# PCB_Slave_Traffic_Light.net
KiCad netlist of a schematic drawn in Altium Designer
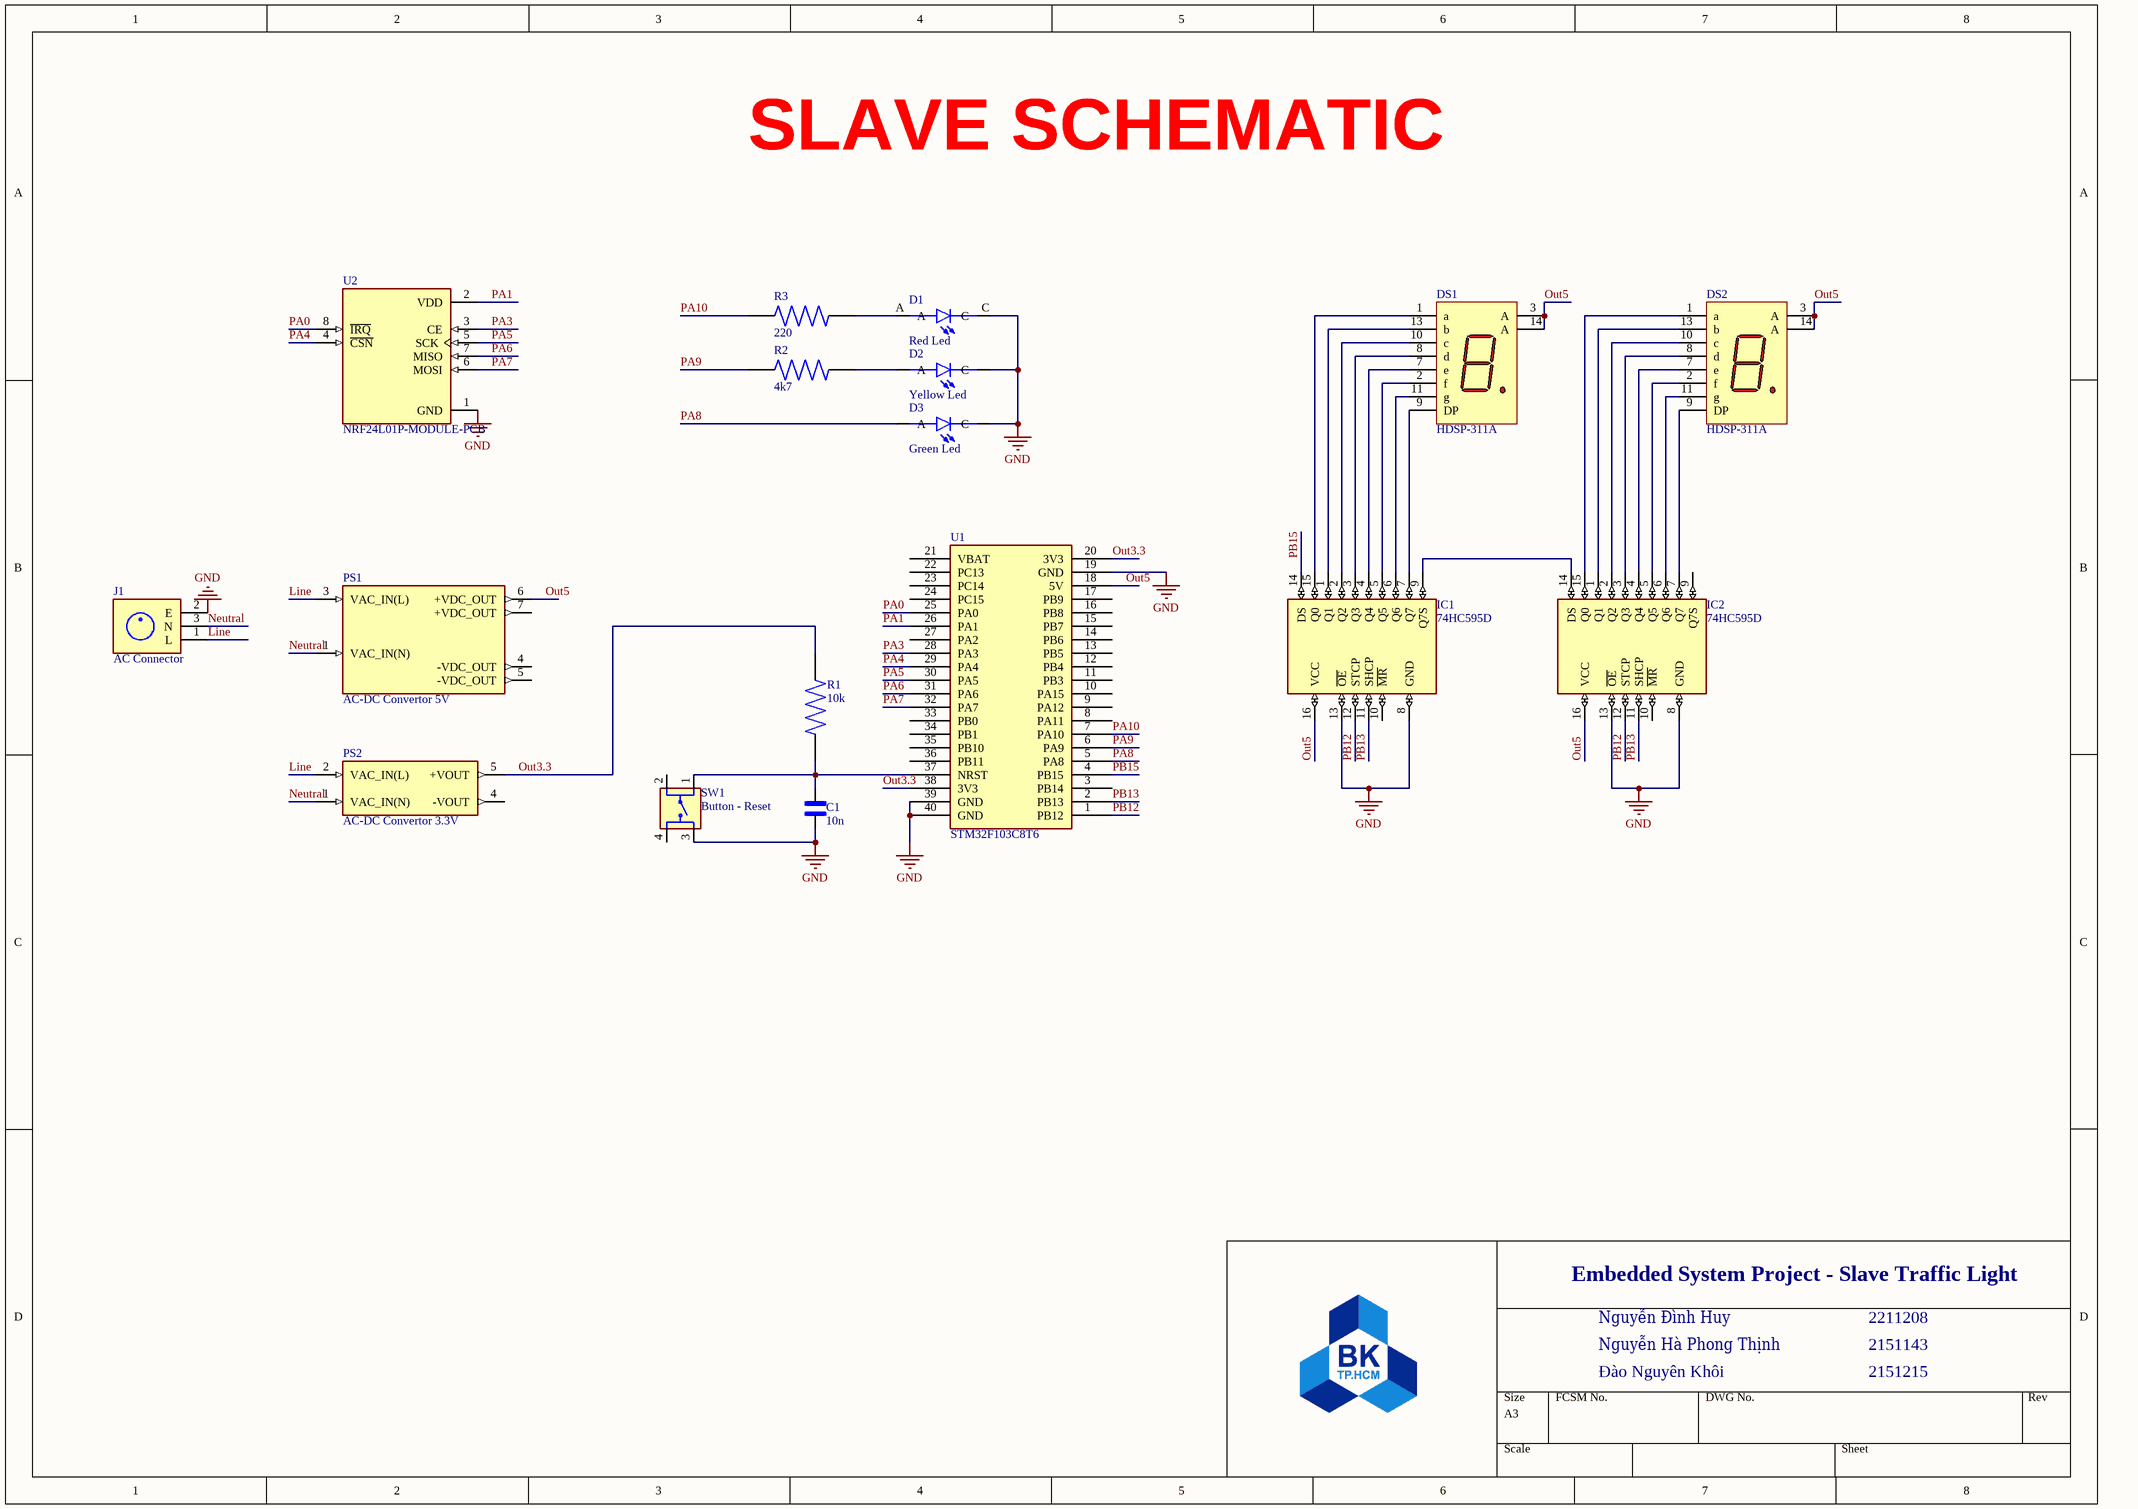
[diagram p0: PCB_Slave_Traffic_Light.SchDoc]

(export (version "E")
  (design (tool "Eeschema 10.0.6"))
  (components
    (comp (ref "C1")
      (value "10n")
      (footprint "CAPC1005X55N")
      (description "Multilayer Ceramic Capacitors MLCC - SMD/SMT")
      (fields (field (name "MF") "Murata") (field (name "MP") "GCM155R11H103KA40D"))
      (libsource (lib "Capacitor 10n") (part "GCM155R11H103KA40D"))
    )
    (comp (ref "D1")
      (value "Red Led")
      (footprint "LED_WP7113ID")
      (description "Red 617nm LED Indication - Discrete 2V Radial")
      (fields (field (name "MP") "WP7113ID") (field (name "MF") "Kingbright"))
      (libsource (lib "Red Led") (part "WP7113ID"))
    )
    (comp (ref "D2")
      (value "Yellow Led")
      (footprint "LED_WP7113SYD")
      (description "Yellow 590nm LED Indication - Discrete 2V Radial")
      (fields (field (name "MF") "Kingbright") (field (name "MP") "WP7113SYD"))
      (libsource (lib "Yellow Led") (part "WP7113SYD"))
    )
    (comp (ref "D3")
      (value "Green Led")
      (footprint "LED_WP7113GD")
      (description "Green 568nm LED Indication - Discrete 2.2V Radial")
      (fields (field (name "MF") "Kingbright") (field (name "MP") "WP7113GD"))
      (libsource (lib "Green Led") (part "WP7113GD"))
    )
    (comp (ref "DS1")
      (value "HDSP-311A")
      (footprint "F-10(14)")
      (description "10.16 mm Single Digit General Purpose AlGaAs Red 7-Segment Display: CA, RH DP")
      (fields (field (name "PUBLISHER") "Altium Limited"))
      (libsource (lib "Agilent LED Display 7-Segment, 1-Digit") (part "HDSP-311A"))
    )
    (comp (ref "DS2")
      (value "HDSP-311A")
      (footprint "F-10(14)")
      (description "10.16 mm Single Digit General Purpose AlGaAs Red 7-Segment Display: CA, RH DP")
      (fields (field (name "PUBLISHER") "Altium Limited"))
      (libsource (lib "Agilent LED Display 7-Segment, 1-Digit") (part "HDSP-311A"))
    )
    (comp (ref "IC1")
      (value "74HC595D")
      (footprint "SOIC127P600X175-16N")
      (description "Shift Register Single 8-Bit Serial to Serial/Parallel 16-Pin SOIC T/R")
      (fields (field (name "MF") "NXP Semiconductors"))
      (libsource (lib "74HC595D") (part "74HC595D"))
    )
    (comp (ref "IC2")
      (value "74HC595D")
      (footprint "SOIC127P600X175-16N")
      (description "Shift Register Single 8-Bit Serial to Serial/Parallel 16-Pin SOIC T/R")
      (fields (field (name "MF") "NXP Semiconductors"))
      (libsource (lib "74HC595D") (part "74HC595D"))
    )
    (comp (ref "J1")
      (value "AC Connector")
      (footprint "QUALTEK_703W-00/52")
      (fields (field (name "MP") "703W-00/52") (field (name "MF") "Qualtek"))
      (libsource (lib "AC Connector") (part "703W-00/52"))
    )
    (comp (ref "PS1")
      (value "AC-DC Convertor 5V")
      (footprint "CONV_RACM40-05SK/OF/PCB-T")
      (description "Open Frame AC DC Converters 1 Uitgang 5V - - - 6A 80 ~ 264 VAC, 120 ~ 370 VDC Input")
      (fields (field (name "MF") "Recom Power") (field (name "MP") "RACM40-05SK/OF/PCB-T"))
      (libsource (lib "AC-DC Converter") (part "RACM40-05SK/OF/PCB-T"))
    )
    (comp (ref "PS2")
      (value "AC-DC Convertor 3.3V")
      (footprint "CONV_RAC10-3.3SK/277")
      (description "10W AC/DC-Converter 'POWERLINE' 2x1 4kV reg")
      (fields (field (name "MF") "Recom Power") (field (name "MP") "RAC10-3.3SK/277"))
      (libsource (lib "AC-DC Converter 3.3V") (part "RAC10-3.3SK/277"))
    )
    (comp (ref "R1")
      (value "10k")
      (footprint "RESC2012X60N")
      (description "10 kOhms Â±1% 0.125W, 1/8W Chip Resistor 0805 (2012 Metric) Moisture Resistant Thick Film")
      (fields (field (name "MF") "Yageo") (field (name "MP") "RC0805FR-0710KL"))
      (libsource (lib "Resistor 10k") (part "RC0805FR-0710KL"))
    )
    (comp (ref "R2")
      (value "4k7")
      (footprint "RESC1608X55N")
      (fields
        (field (name "MF") "TE Connectivity")
        (field (name "MP") "CRG0603F4K7")
        (field (name "TOLERANCE") "1%")
      )
      (libsource (lib "RES4.7k") (part "CRG0603F4K7"))
    )
    (comp (ref "R3")
      (value "220")
      (footprint "RESC6332X120N")
      (description "220 Ohms Â±1% 3W Chip Resistor 2512 (6432 Metric) Automotive AEC-Q200 Thick Film")
      (fields (field (name "MF") "TE Connectivity") (field (name "MP") "3522220RFT"))
      (libsource (lib "Resistor 200Ohm") (part "3522220RFT"))
    )
    (comp (ref "SW1")
      (value "Button - Reset")
      (footprint "SW_FSM8JH")
      (description "Tactile Switch SPST-NO Top Actuated Through Hole")
      (fields (field (name "MP") "FSM8JH") (field (name "MF") "TE Connectivity"))
      (libsource (lib "Button1") (part "FSM8JH"))
    )
    (comp (ref "U1")
      (value "STM32F103C8T6")
      (footprint "Stm32 BluePill")
      (description "Designed By @Alixahedi")
      (libsource (lib "Stm32 Blue Pill") (part "BluePill"))
    )
    (comp (ref "U2")
      (value "NRF24L01P-MODULE-PCB")
      (footprint "XCVR_NRF24L01P-MODULE-PCB")
      (description "- Transceiver For Use With nRF24L01+")
      (fields (field (name "MF") "Nordic Semiconductor"))
      (libsource (lib "NRF24L01P-MODULE-PCB") (part "NRF24L01P-MODULE-PCB"))
    )
  )
  (nets
    (net (code "1") (name "/Line") (class "Default")
      (node (ref "J1") (pin "1") (pinfunction "L_1") (pintype "power_in"))
      (node (ref "PS1") (pin "3") (pinfunction "VAC_IN(L)_3") (pintype "input"))
      (node (ref "PS2") (pin "2") (pinfunction "VAC_IN(L)_2") (pintype "input"))
    )
    (net (code "2") (name "/Neutral") (class "Default")
      (node (ref "J1") (pin "3") (pinfunction "N_3") (pintype "power_in"))
      (node (ref "PS1") (pin "1") (pinfunction "VAC_IN(N)_1") (pintype "input"))
      (node (ref "PS2") (pin "1") (pinfunction "VAC_IN(N)_1") (pintype "input"))
    )
    (net (code "3") (name "/Out3.3") (class "Default")
      (node (ref "PS2") (pin "5") (pinfunction "+VOUT_5") (pintype "output"))
      (node (ref "R1") (pin "1") (pinfunction "1_1") (pintype "passive"))
      (node (ref "U1") (pin "20") (pinfunction "3V3_20") (pintype "passive"))
      (node (ref "U1") (pin "38") (pinfunction "3V3_38") (pintype "passive"))
    )
    (net (code "4") (name "/Out5") (class "Default")
      (node (ref "DS1") (pin "14") (pinfunction "A_14") (pintype "passive"))
      (node (ref "DS1") (pin "3") (pinfunction "A_3") (pintype "passive"))
      (node (ref "DS2") (pin "14") (pinfunction "A_14") (pintype "passive"))
      (node (ref "DS2") (pin "3") (pinfunction "A_3") (pintype "passive"))
      (node (ref "IC1") (pin "16") (pinfunction "VCC_16") (pintype "bidirectional"))
      (node (ref "IC2") (pin "16") (pinfunction "VCC_16") (pintype "bidirectional"))
      (node (ref "PS1") (pin "6") (pinfunction "+VDC_OUT_6") (pintype "output"))
      (node (ref "U1") (pin "18") (pinfunction "5V_18") (pintype "passive"))
    )
    (net (code "5") (name "/PA0") (class "Default")
      (node (ref "U1") (pin "25") (pinfunction "PA0_25") (pintype "passive"))
      (node (ref "U2") (pin "8") (pinfunction "~{IRQ}_8") (pintype "input"))
    )
    (net (code "6") (name "/PA1") (class "Default")
      (node (ref "U1") (pin "26") (pinfunction "PA1_26") (pintype "passive"))
      (node (ref "U2") (pin "2") (pinfunction "VDD_2") (pintype "power_in"))
    )
    (net (code "7") (name "/PA3") (class "Default")
      (node (ref "U1") (pin "28") (pinfunction "PA3_28") (pintype "passive"))
      (node (ref "U2") (pin "3") (pinfunction "CE_3") (pintype "input"))
    )
    (net (code "8") (name "/PA4") (class "Default")
      (node (ref "U1") (pin "29") (pinfunction "PA4_29") (pintype "passive"))
      (node (ref "U2") (pin "4") (pinfunction "~{CSN}_4") (pintype "input"))
    )
    (net (code "9") (name "/PA5") (class "Default")
      (node (ref "U1") (pin "30") (pinfunction "PA5_30") (pintype "passive"))
      (node (ref "U2") (pin "5") (pinfunction "SCK_5") (pintype "input"))
    )
    (net (code "10") (name "/PA6") (class "Default")
      (node (ref "U1") (pin "31") (pinfunction "PA6_31") (pintype "passive"))
      (node (ref "U2") (pin "7") (pinfunction "MISO_7") (pintype "input"))
    )
    (net (code "11") (name "/PA7") (class "Default")
      (node (ref "U1") (pin "32") (pinfunction "PA7_32") (pintype "passive"))
      (node (ref "U2") (pin "6") (pinfunction "MOSI_6") (pintype "input"))
    )
    (net (code "12") (name "/PA8") (class "Default")
      (node (ref "D3") (pin "A") (pinfunction "A_A") (pintype "passive"))
      (node (ref "U1") (pin "5") (pinfunction "PA8_5") (pintype "passive"))
    )
    (net (code "13") (name "/PA9") (class "Default")
      (node (ref "R2") (pin "1") (pinfunction "1_1") (pintype "passive"))
      (node (ref "U1") (pin "6") (pinfunction "PA9_6") (pintype "passive"))
    )
    (net (code "14") (name "/PA10") (class "Default")
      (node (ref "R3") (pin "1") (pinfunction "1_1") (pintype "passive"))
      (node (ref "U1") (pin "7") (pinfunction "PA10_7") (pintype "passive"))
    )
    (net (code "15") (name "/PB12") (class "Default")
      (node (ref "IC1") (pin "12") (pinfunction "STCP_12") (pintype "bidirectional"))
      (node (ref "IC2") (pin "12") (pinfunction "STCP_12") (pintype "bidirectional"))
      (node (ref "U1") (pin "1") (pinfunction "PB12_1") (pintype "passive"))
    )
    (net (code "16") (name "/PB13") (class "Default")
      (node (ref "IC1") (pin "11") (pinfunction "SHCP_11") (pintype "bidirectional"))
      (node (ref "IC2") (pin "11") (pinfunction "SHCP_11") (pintype "bidirectional"))
      (node (ref "U1") (pin "2") (pinfunction "PB13_2") (pintype "passive"))
    )
    (net (code "17") (name "/PB15") (class "Default")
      (node (ref "IC1") (pin "14") (pinfunction "DS_14") (pintype "bidirectional"))
      (node (ref "U1") (pin "4") (pinfunction "PB15_4") (pintype "passive"))
    )
    (net (code "18") (name "GND") (class "Default")
      (node (ref "C1") (pin "1") (pinfunction "1_1") (pintype "passive"))
      (node (ref "D1") (pin "C") (pinfunction "C_C") (pintype "passive"))
      (node (ref "D2") (pin "C") (pinfunction "C_C") (pintype "passive"))
      (node (ref "D3") (pin "C") (pinfunction "C_C") (pintype "passive"))
      (node (ref "IC1") (pin "13") (pinfunction "~{OE}_13") (pintype "bidirectional"))
      (node (ref "IC1") (pin "8") (pinfunction "GND_8") (pintype "bidirectional"))
      (node (ref "IC2") (pin "13") (pinfunction "~{OE}_13") (pintype "bidirectional"))
      (node (ref "IC2") (pin "8") (pinfunction "GND_8") (pintype "bidirectional"))
      (node (ref "J1") (pin "2") (pinfunction "E_2") (pintype "power_in"))
      (node (ref "SW1") (pin "3") (pinfunction "3_3") (pintype "passive"))
      (node (ref "U1") (pin "19") (pinfunction "GND_19") (pintype "passive"))
      (node (ref "U1") (pin "39") (pinfunction "GND_39") (pintype "passive"))
      (node (ref "U1") (pin "40") (pinfunction "GND_40") (pintype "passive"))
      (node (ref "U2") (pin "1") (pinfunction "GND_1") (pintype "power_in"))
    )
    (net (code "19") (name "Net-(D1-PadA)") (class "Default")
      (node (ref "D1") (pin "A") (pinfunction "A_A") (pintype "passive"))
      (node (ref "R3") (pin "2") (pinfunction "2_2") (pintype "passive"))
    )
    (net (code "20") (name "Net-(D2-PadA)") (class "Default")
      (node (ref "D2") (pin "A") (pinfunction "A_A") (pintype "passive"))
      (node (ref "R2") (pin "2") (pinfunction "2_2") (pintype "passive"))
    )
    (net (code "21") (name "Net-(DS1-DP)") (class "Default")
      (node (ref "DS1") (pin "9") (pinfunction "DP_9") (pintype "passive"))
      (node (ref "IC1") (pin "7") (pinfunction "Q7_7") (pintype "bidirectional"))
    )
    (net (code "22") (name "Net-(DS1-a)") (class "Default")
      (node (ref "DS1") (pin "1") (pinfunction "a_1") (pintype "passive"))
      (node (ref "IC1") (pin "15") (pinfunction "Q0_15") (pintype "bidirectional"))
    )
    (net (code "23") (name "Net-(DS1-b)") (class "Default")
      (node (ref "DS1") (pin "13") (pinfunction "b_13") (pintype "passive"))
      (node (ref "IC1") (pin "1") (pinfunction "Q1_1") (pintype "bidirectional"))
    )
    (net (code "24") (name "Net-(DS1-c)") (class "Default")
      (node (ref "DS1") (pin "10") (pinfunction "c_10") (pintype "passive"))
      (node (ref "IC1") (pin "2") (pinfunction "Q2_2") (pintype "bidirectional"))
    )
    (net (code "25") (name "Net-(DS1-d)") (class "Default")
      (node (ref "DS1") (pin "8") (pinfunction "d_8") (pintype "passive"))
      (node (ref "IC1") (pin "3") (pinfunction "Q3_3") (pintype "bidirectional"))
    )
    (net (code "26") (name "Net-(DS1-e)") (class "Default")
      (node (ref "DS1") (pin "7") (pinfunction "e_7") (pintype "passive"))
      (node (ref "IC1") (pin "4") (pinfunction "Q4_4") (pintype "bidirectional"))
    )
    (net (code "27") (name "Net-(DS1-f)") (class "Default")
      (node (ref "DS1") (pin "2") (pinfunction "f_2") (pintype "passive"))
      (node (ref "IC1") (pin "5") (pinfunction "Q5_5") (pintype "bidirectional"))
    )
    (net (code "28") (name "Net-(DS1-g)") (class "Default")
      (node (ref "DS1") (pin "11") (pinfunction "g_11") (pintype "passive"))
      (node (ref "IC1") (pin "6") (pinfunction "Q6_6") (pintype "bidirectional"))
    )
    (net (code "29") (name "Net-(DS2-DP)") (class "Default")
      (node (ref "DS2") (pin "9") (pinfunction "DP_9") (pintype "passive"))
      (node (ref "IC2") (pin "7") (pinfunction "Q7_7") (pintype "bidirectional"))
    )
    (net (code "30") (name "Net-(DS2-a)") (class "Default")
      (node (ref "DS2") (pin "1") (pinfunction "a_1") (pintype "passive"))
      (node (ref "IC2") (pin "15") (pinfunction "Q0_15") (pintype "bidirectional"))
    )
    (net (code "31") (name "Net-(DS2-b)") (class "Default")
      (node (ref "DS2") (pin "13") (pinfunction "b_13") (pintype "passive"))
      (node (ref "IC2") (pin "1") (pinfunction "Q1_1") (pintype "bidirectional"))
    )
    (net (code "32") (name "Net-(DS2-c)") (class "Default")
      (node (ref "DS2") (pin "10") (pinfunction "c_10") (pintype "passive"))
      (node (ref "IC2") (pin "2") (pinfunction "Q2_2") (pintype "bidirectional"))
    )
    (net (code "33") (name "Net-(DS2-d)") (class "Default")
      (node (ref "DS2") (pin "8") (pinfunction "d_8") (pintype "passive"))
      (node (ref "IC2") (pin "3") (pinfunction "Q3_3") (pintype "bidirectional"))
    )
    (net (code "34") (name "Net-(DS2-e)") (class "Default")
      (node (ref "DS2") (pin "7") (pinfunction "e_7") (pintype "passive"))
      (node (ref "IC2") (pin "4") (pinfunction "Q4_4") (pintype "bidirectional"))
    )
    (net (code "35") (name "Net-(DS2-f)") (class "Default")
      (node (ref "DS2") (pin "2") (pinfunction "f_2") (pintype "passive"))
      (node (ref "IC2") (pin "5") (pinfunction "Q5_5") (pintype "bidirectional"))
    )
    (net (code "36") (name "Net-(DS2-g)") (class "Default")
      (node (ref "DS2") (pin "11") (pinfunction "g_11") (pintype "passive"))
      (node (ref "IC2") (pin "6") (pinfunction "Q6_6") (pintype "bidirectional"))
    )
    (net (code "37") (name "Net-(IC1-Q7S)") (class "Default")
      (node (ref "IC1") (pin "9") (pinfunction "Q7S_9") (pintype "bidirectional"))
      (node (ref "IC2") (pin "14") (pinfunction "DS_14") (pintype "bidirectional"))
    )
    (net (code "38") (name "Net-(U1-NRST)") (class "Default")
      (node (ref "C1") (pin "2") (pinfunction "2_2") (pintype "passive"))
      (node (ref "R1") (pin "2") (pinfunction "2_2") (pintype "passive"))
      (node (ref "SW1") (pin "1") (pinfunction "1_1") (pintype "passive"))
      (node (ref "U1") (pin "37") (pinfunction "NRST_37") (pintype "passive"))
    )
    (net (code "39") (name "unconnected-(IC1-~{MR}-Pad10)") (class "Default")
      (node (ref "IC1") (pin "10") (pinfunction "~{MR}_10") (pintype "bidirectional"))
    )
    (net (code "40") (name "unconnected-(IC2-Q7S-Pad9)") (class "Default")
      (node (ref "IC2") (pin "9") (pinfunction "Q7S_9") (pintype "bidirectional"))
    )
    (net (code "41") (name "unconnected-(IC2-~{MR}-Pad10)") (class "Default")
      (node (ref "IC2") (pin "10") (pinfunction "~{MR}_10") (pintype "bidirectional"))
    )
    (net (code "42") (name "unconnected-(PS1-+VDC_OUT-Pad7)") (class "Default")
      (node (ref "PS1") (pin "7") (pinfunction "+VDC_OUT_7") (pintype "output"))
    )
    (net (code "43") (name "unconnected-(PS1--VDC_OUT-Pad4)") (class "Default")
      (node (ref "PS1") (pin "4") (pinfunction "-VDC_OUT_4") (pintype "output"))
    )
    (net (code "44") (name "unconnected-(PS1--VDC_OUT-Pad5)") (class "Default")
      (node (ref "PS1") (pin "5") (pinfunction "-VDC_OUT_5") (pintype "output"))
    )
    (net (code "45") (name "unconnected-(PS2--VOUT-Pad4)") (class "Default")
      (node (ref "PS2") (pin "4") (pinfunction "-VOUT_4") (pintype "output"))
    )
    (net (code "46") (name "unconnected-(SW1-Pad2)") (class "Default")
      (node (ref "SW1") (pin "2") (pinfunction "2_2") (pintype "passive"))
    )
    (net (code "47") (name "unconnected-(SW1-Pad4)") (class "Default")
      (node (ref "SW1") (pin "4") (pinfunction "4_4") (pintype "passive"))
    )
    (net (code "48") (name "unconnected-(U1-PA2-Pad27)") (class "Default")
      (node (ref "U1") (pin "27") (pinfunction "PA2_27") (pintype "passive"))
    )
    (net (code "49") (name "unconnected-(U1-PA11-Pad8)") (class "Default")
      (node (ref "U1") (pin "8") (pinfunction "PA11_8") (pintype "passive"))
    )
    (net (code "50") (name "unconnected-(U1-PA12-Pad9)") (class "Default")
      (node (ref "U1") (pin "9") (pinfunction "PA12_9") (pintype "passive"))
    )
    (net (code "51") (name "unconnected-(U1-PA15-Pad10)") (class "Default")
      (node (ref "U1") (pin "10") (pinfunction "PA15_10") (pintype "passive"))
    )
    (net (code "52") (name "unconnected-(U1-PB0-Pad33)") (class "Default")
      (node (ref "U1") (pin "33") (pinfunction "PB0_33") (pintype "passive"))
    )
    (net (code "53") (name "unconnected-(U1-PB1-Pad34)") (class "Default")
      (node (ref "U1") (pin "34") (pinfunction "PB1_34") (pintype "passive"))
    )
    (net (code "54") (name "unconnected-(U1-PB3-Pad11)") (class "Default")
      (node (ref "U1") (pin "11") (pinfunction "PB3_11") (pintype "passive"))
    )
    (net (code "55") (name "unconnected-(U1-PB4-Pad12)") (class "Default")
      (node (ref "U1") (pin "12") (pinfunction "PB4_12") (pintype "passive"))
    )
    (net (code "56") (name "unconnected-(U1-PB5-Pad13)") (class "Default")
      (node (ref "U1") (pin "13") (pinfunction "PB5_13") (pintype "passive"))
    )
    (net (code "57") (name "unconnected-(U1-PB6-Pad14)") (class "Default")
      (node (ref "U1") (pin "14") (pinfunction "PB6_14") (pintype "passive"))
    )
    (net (code "58") (name "unconnected-(U1-PB7-Pad15)") (class "Default")
      (node (ref "U1") (pin "15") (pinfunction "PB7_15") (pintype "passive"))
    )
    (net (code "59") (name "unconnected-(U1-PB8-Pad16)") (class "Default")
      (node (ref "U1") (pin "16") (pinfunction "PB8_16") (pintype "passive"))
    )
    (net (code "60") (name "unconnected-(U1-PB9-Pad17)") (class "Default")
      (node (ref "U1") (pin "17") (pinfunction "PB9_17") (pintype "passive"))
    )
    (net (code "61") (name "unconnected-(U1-PB10-Pad35)") (class "Default")
      (node (ref "U1") (pin "35") (pinfunction "PB10_35") (pintype "passive"))
    )
    (net (code "62") (name "unconnected-(U1-PB11-Pad36)") (class "Default")
      (node (ref "U1") (pin "36") (pinfunction "PB11_36") (pintype "passive"))
    )
    (net (code "63") (name "unconnected-(U1-PB14-Pad3)") (class "Default")
      (node (ref "U1") (pin "3") (pinfunction "PB14_3") (pintype "passive"))
    )
    (net (code "64") (name "unconnected-(U1-PC13-Pad22)") (class "Default")
      (node (ref "U1") (pin "22") (pinfunction "PC13_22") (pintype "passive"))
    )
    (net (code "65") (name "unconnected-(U1-PC14-Pad23)") (class "Default")
      (node (ref "U1") (pin "23") (pinfunction "PC14_23") (pintype "passive"))
    )
    (net (code "66") (name "unconnected-(U1-PC15-Pad24)") (class "Default")
      (node (ref "U1") (pin "24") (pinfunction "PC15_24") (pintype "passive"))
    )
    (net (code "67") (name "unconnected-(U1-VBAT-Pad21)") (class "Default")
      (node (ref "U1") (pin "21") (pinfunction "VBAT_21") (pintype "passive"))
    )
  )
)
